# 02_Connectors.net
KiCad netlist of a schematic drawn in Altium Designer
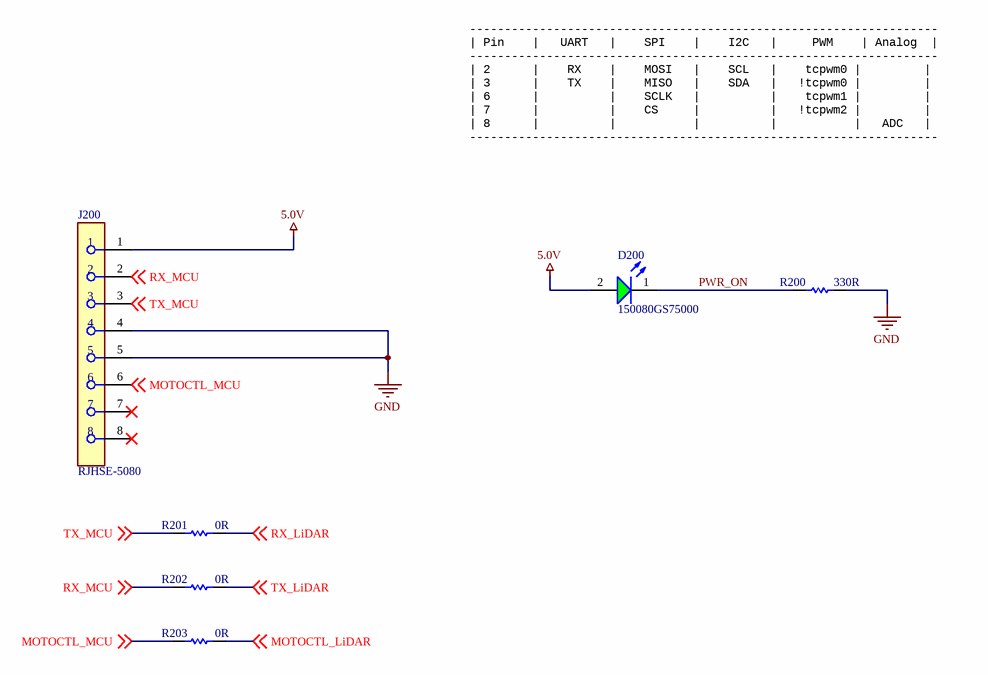
[diagram p0: 02_Connectors.SchDoc]

(export (version "E")
  (design (tool "Eeschema 10.0.6"))
  (components
    (comp (ref "D200")
      (value "150080GS75000")
      (footprint "WL-SMCW_0805_150080xx75000")
      (fields (field (name "MANUFACTURER") "Wurth Electronics"))
      (libsource (lib "Altium Content Vault") (part "LED_Green_2A-1K"))
    )
    (comp (ref "J200")
      (value "RJHSE-5080")
      (footprint "FP-RJHSE-5080-MFG")
      (description "CONN MOD JACK 8P8C R/A UNSHLD")
      (fields
        (field (name "OCTOPART") "https://octopart.com/rjhse-5080-amphenol-45060")
        (field (name "MANUFACTURER") "Amphenol")
      )
      (libsource (lib "Altium Content Vault") (part "b0a0b555dd3abf3683e7c330df25cc4"))
    )
    (comp (ref "R200")
      (value "330R")
      (footprint "RESC2013X60X40LL20T25")
      (fields
        (field (name "MANUFACTURER") "Panasonic")
        (field (name "PART NUMBER") "ERA6AEB331V")
        (field (name "MANUFACTURER PART NUMBER") "ERA-6AEB331V")
      )
      (libsource (lib "Altium Content Vault") (part "RES"))
    )
    (comp (ref "R201")
      (value "0R")
      (footprint "RESC2013X70X40NL20T20")
      (description "Chip Resistor, 0 Ohm, +/- 1%, 0.125 W, -55 to 155 degC, 0805 (2012 Metric), RoHS, Tape and Reel")
      (fields (field (name "PARTNUMBER") "ERJ-6GEY0R00V") (field (name "TOLERANCE") "5%"))
      (libsource (lib "Altium Content Vault") (part "RES-2"))
    )
    (comp (ref "R202")
      (value "0R")
      (footprint "RESC2013X70X40NL20T20")
      (description "Chip Resistor, 0 Ohm, +/- 1%, 0.125 W, -55 to 155 degC, 0805 (2012 Metric), RoHS, Tape and Reel")
      (fields (field (name "PARTNUMBER") "ERJ-6GEY0R00V") (field (name "TOLERANCE") "5%"))
      (libsource (lib "Altium Content Vault") (part "RES-2"))
    )
    (comp (ref "R203")
      (value "0R")
      (footprint "RESC2013X70X40NL20T20")
      (description "Chip Resistor, 0 Ohm, +/- 1%, 0.125 W, -55 to 155 degC, 0805 (2012 Metric), RoHS, Tape and Reel")
      (fields (field (name "PARTNUMBER") "ERJ-6GEY0R00V") (field (name "TOLERANCE") "5%"))
      (libsource (lib "Altium Content Vault") (part "RES-2"))
    )
  )
  (nets
    (net (code "1") (name "/PWR_ON") (class "Default")
      (node (ref "D200") (pin "1") (pinfunction "K_1") (pintype "passive"))
      (node (ref "R200") (pin "1") (pinfunction "1_1") (pintype "passive"))
    )
    (net (code "2") (name "5.0V") (class "Default")
      (node (ref "D200") (pin "2") (pinfunction "A_2") (pintype "passive"))
      (node (ref "J200") (pin "1") (pinfunction "1_1") (pintype "passive"))
    )
    (net (code "3") (name "GND") (class "Default")
      (node (ref "J200") (pin "4") (pinfunction "4_4") (pintype "passive"))
      (node (ref "J200") (pin "5") (pinfunction "5_5") (pintype "passive"))
      (node (ref "R200") (pin "2") (pinfunction "2_2") (pintype "passive"))
    )
    (net (code "4") (name "MOTOCTL_LiDAR") (class "Default")
      (node (ref "R203") (pin "2") (pinfunction "2_2") (pintype "passive"))
    )
    (net (code "5") (name "MOTOCTL_MCU") (class "Default")
      (node (ref "J200") (pin "6") (pinfunction "6_6") (pintype "passive"))
      (node (ref "R203") (pin "1") (pinfunction "1_1") (pintype "passive"))
    )
    (net (code "6") (name "RX_LiDAR") (class "Default")
      (node (ref "R201") (pin "2") (pinfunction "2_2") (pintype "passive"))
    )
    (net (code "7") (name "RX_MCU") (class "Default")
      (node (ref "J200") (pin "2") (pinfunction "2_2") (pintype "passive"))
      (node (ref "R202") (pin "1") (pinfunction "1_1") (pintype "passive"))
    )
    (net (code "8") (name "TX_LiDAR") (class "Default")
      (node (ref "R202") (pin "2") (pinfunction "2_2") (pintype "passive"))
    )
    (net (code "9") (name "TX_MCU") (class "Default")
      (node (ref "J200") (pin "3") (pinfunction "3_3") (pintype "passive"))
      (node (ref "R201") (pin "1") (pinfunction "1_1") (pintype "passive"))
    )
    (net (code "10") (name "unconnected-(J200-Pad7)") (class "Default")
      (node (ref "J200") (pin "7") (pinfunction "7_7") (pintype "passive+no_connect"))
    )
    (net (code "11") (name "unconnected-(J200-Pad8)") (class "Default")
      (node (ref "J200") (pin "8") (pinfunction "8_8") (pintype "passive+no_connect"))
    )
  )
)
